# Dirth_Rims_Mend_Orca.net
KiCad netlist of a schematic drawn in EAGLE
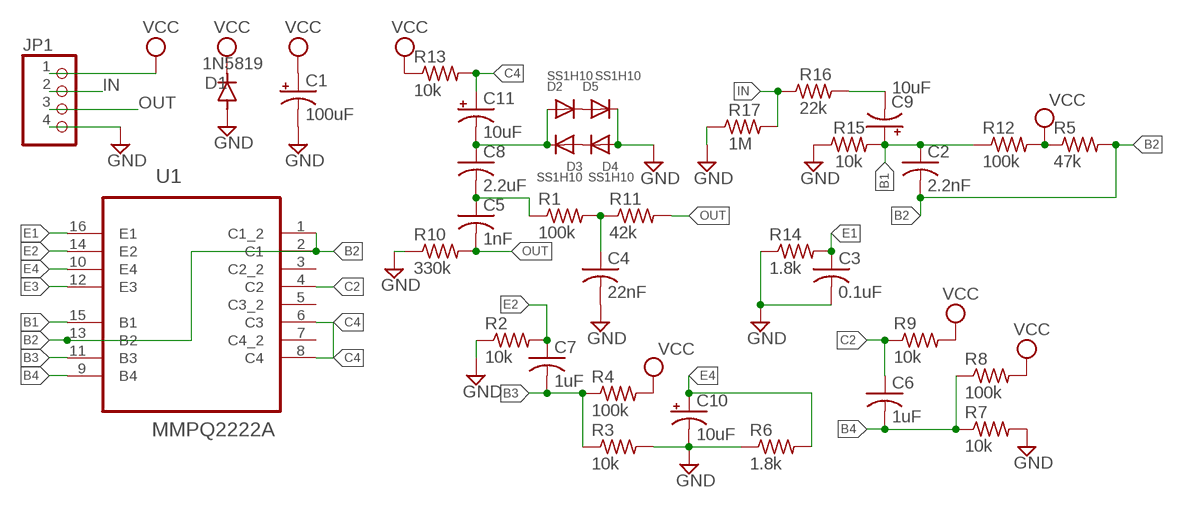
[diagram p0: schematic, sheet 1]

(export (version "E")
  (design (tool "Eeschema 10.0.6"))
  (components
    (comp (ref "C1")
      (value "100uF")
      (footprint "eagle-import:PAN_B_SMD+THRU")
      (libsource (lib "eagle-import") (part "CAP_SMD+THRUPAN_B"))
    )
    (comp (ref "C2")
      (value "2.2nF")
      (footprint "eagle-import:C0603")
      (libsource (lib "eagle-import") (part "C-USC0603"))
    )
    (comp (ref "C3")
      (value "0.1uF")
      (footprint "eagle-import:C0603")
      (libsource (lib "eagle-import") (part "C-USC0603"))
    )
    (comp (ref "C4")
      (value "22nF")
      (footprint "eagle-import:C0603")
      (libsource (lib "eagle-import") (part "C-USC0603"))
    )
    (comp (ref "C5")
      (value "1nF")
      (footprint "eagle-import:C0603")
      (libsource (lib "eagle-import") (part "C-USC0603"))
    )
    (comp (ref "C6")
      (value "1uF")
      (footprint "eagle-import:C0603")
      (libsource (lib "eagle-import") (part "C-USC0603"))
    )
    (comp (ref "C7")
      (value "1uF")
      (footprint "eagle-import:C0603")
      (libsource (lib "eagle-import") (part "C-USC0603"))
    )
    (comp (ref "C8")
      (value "2.2uF")
      (footprint "eagle-import:C0603")
      (libsource (lib "eagle-import") (part "C-USC0603"))
    )
    (comp (ref "C9")
      (value "10uF")
      (footprint "eagle-import:PAN_B_SMD+THRU")
      (libsource (lib "eagle-import") (part "CAP_SMD+THRUPAN_B"))
    )
    (comp (ref "C10")
      (value "10uF")
      (footprint "eagle-import:PAN_B_SMD+THRU")
      (libsource (lib "eagle-import") (part "CAP_SMD+THRUPAN_B"))
    )
    (comp (ref "C11")
      (value "10uF")
      (footprint "eagle-import:PAN_B_SMD+THRU")
      (libsource (lib "eagle-import") (part "CAP_SMD+THRUPAN_B"))
    )
    (comp (ref "D1")
      (value "1N5819")
      (footprint "eagle-import:SOD123")
      (libsource (lib "eagle-import") (part "DIODE-SOD123"))
    )
    (comp (ref "D2")
      (value "SS1H10")
      (footprint "eagle-import:SMADIODE")
      (libsource (lib "eagle-import") (part "DIODESMA"))
    )
    (comp (ref "D3")
      (value "SS1H10")
      (footprint "eagle-import:SMADIODE")
      (libsource (lib "eagle-import") (part "DIODESMA"))
    )
    (comp (ref "D4")
      (value "SS1H10")
      (footprint "eagle-import:SMADIODE")
      (libsource (lib "eagle-import") (part "DIODESMA"))
    )
    (comp (ref "D5")
      (value "SS1H10")
      (footprint "eagle-import:SMADIODE")
      (libsource (lib "eagle-import") (part "DIODESMA"))
    )
    (comp (ref "JP1")
      (value "PINHD-1X4")
      (footprint "eagle-import:1X04")
      (libsource (lib "eagle-import") (part "PINHD-1X4"))
    )
    (comp (ref "R1")
      (value "100k")
      (footprint "eagle-import:R0603")
      (libsource (lib "eagle-import") (part "R-US_R0603"))
    )
    (comp (ref "R2")
      (value "10k")
      (footprint "eagle-import:R0603")
      (libsource (lib "eagle-import") (part "R-US_R0603"))
    )
    (comp (ref "R3")
      (value "10k")
      (footprint "eagle-import:R0603")
      (libsource (lib "eagle-import") (part "R-US_R0603"))
    )
    (comp (ref "R4")
      (value "100k")
      (footprint "eagle-import:R0603")
      (libsource (lib "eagle-import") (part "R-US_R0603"))
    )
    (comp (ref "R5")
      (value "47k")
      (footprint "eagle-import:R0603")
      (libsource (lib "eagle-import") (part "R-US_R0603"))
    )
    (comp (ref "R6")
      (value "1.8k")
      (footprint "eagle-import:R0603")
      (libsource (lib "eagle-import") (part "R-US_R0603"))
    )
    (comp (ref "R7")
      (value "10k")
      (footprint "eagle-import:R0603")
      (libsource (lib "eagle-import") (part "R-US_R0603"))
    )
    (comp (ref "R8")
      (value "100k")
      (footprint "eagle-import:R0603")
      (libsource (lib "eagle-import") (part "R-US_R0603"))
    )
    (comp (ref "R9")
      (value "10k")
      (footprint "eagle-import:R0603")
      (libsource (lib "eagle-import") (part "R-US_R0603"))
    )
    (comp (ref "R10")
      (value "330k")
      (footprint "eagle-import:R0603")
      (libsource (lib "eagle-import") (part "R-US_R0603"))
    )
    (comp (ref "R11")
      (value "42k")
      (footprint "eagle-import:R0603")
      (libsource (lib "eagle-import") (part "R-US_R0603"))
    )
    (comp (ref "R12")
      (value "100k")
      (footprint "eagle-import:R0603")
      (libsource (lib "eagle-import") (part "R-US_R0603"))
    )
    (comp (ref "R13")
      (value "10k")
      (footprint "eagle-import:R0603")
      (libsource (lib "eagle-import") (part "R-US_R0603"))
    )
    (comp (ref "R14")
      (value "1.8k")
      (footprint "eagle-import:R0603")
      (libsource (lib "eagle-import") (part "R-US_R0603"))
    )
    (comp (ref "R15")
      (value "10k")
      (footprint "eagle-import:R0603")
      (libsource (lib "eagle-import") (part "R-US_R0603"))
    )
    (comp (ref "R16")
      (value "22k")
      (footprint "eagle-import:R0603")
      (libsource (lib "eagle-import") (part "R-US_R0603"))
    )
    (comp (ref "R17")
      (value "1M")
      (footprint "eagle-import:R0603")
      (libsource (lib "eagle-import") (part "R-US_R0603"))
    )
    (comp (ref "U1")
      (value "MMPQ2222A")
      (footprint "eagle-import:SOIC127P600X175-16N")
      (fields (field (name "MF") "ON Semiconductor"))
      (libsource (lib "eagle-import") (part "MMPQ2222A"))
    )
  )
  (nets
    (net (code "1") (name "B1") (class "Default")
      (node (ref "C2") (pin "1") (pinfunction "1_1") (pintype "passive"))
      (node (ref "C9") (pin "+") (pinfunction "+_+") (pintype "passive"))
      (node (ref "C9") (pin "++") (pinfunction "+_++") (pintype "passive"))
      (node (ref "R12") (pin "1") (pinfunction "1_1") (pintype "passive"))
      (node (ref "R15") (pin "2") (pinfunction "2_2") (pintype "passive"))
      (node (ref "U1") (pin "15") (pinfunction "B1_15") (pintype "passive"))
    )
    (net (code "2") (name "B2") (class "Default")
      (node (ref "C2") (pin "2") (pinfunction "2_2") (pintype "passive"))
      (node (ref "R5") (pin "2") (pinfunction "2_2") (pintype "passive"))
      (node (ref "U1") (pin "1") (pinfunction "C1_2_1") (pintype "passive"))
      (node (ref "U1") (pin "13") (pinfunction "B2_13") (pintype "passive"))
      (node (ref "U1") (pin "2") (pinfunction "C1_2") (pintype "passive"))
    )
    (net (code "3") (name "B3") (class "Default")
      (node (ref "C7") (pin "2") (pinfunction "2_2") (pintype "passive"))
      (node (ref "R3") (pin "1") (pinfunction "1_1") (pintype "passive"))
      (node (ref "R4") (pin "1") (pinfunction "1_1") (pintype "passive"))
      (node (ref "U1") (pin "11") (pinfunction "B3_11") (pintype "passive"))
    )
    (net (code "4") (name "B4") (class "Default")
      (node (ref "C6") (pin "2") (pinfunction "2_2") (pintype "passive"))
      (node (ref "R7") (pin "1") (pinfunction "1_1") (pintype "passive"))
      (node (ref "R8") (pin "1") (pinfunction "1_1") (pintype "passive"))
      (node (ref "U1") (pin "9") (pinfunction "B4_9") (pintype "passive"))
    )
    (net (code "5") (name "C2") (class "Default")
      (node (ref "C6") (pin "1") (pinfunction "1_1") (pintype "passive"))
      (node (ref "R9") (pin "1") (pinfunction "1_1") (pintype "passive"))
      (node (ref "U1") (pin "4") (pinfunction "C2_4") (pintype "passive"))
    )
    (net (code "6") (name "C4") (class "Default")
      (node (ref "C11") (pin "+") (pinfunction "+_+") (pintype "passive"))
      (node (ref "C11") (pin "++") (pinfunction "+_++") (pintype "passive"))
      (node (ref "R13") (pin "2") (pinfunction "2_2") (pintype "passive"))
      (node (ref "U1") (pin "6") (pinfunction "C3_6") (pintype "passive"))
      (node (ref "U1") (pin "8") (pinfunction "C4_8") (pintype "passive"))
    )
    (net (code "7") (name "E1") (class "Default")
      (node (ref "C3") (pin "1") (pinfunction "1_1") (pintype "passive"))
      (node (ref "R14") (pin "2") (pinfunction "2_2") (pintype "passive"))
      (node (ref "U1") (pin "16") (pinfunction "E1_16") (pintype "passive"))
    )
    (net (code "8") (name "E2") (class "Default")
      (node (ref "C7") (pin "1") (pinfunction "1_1") (pintype "passive"))
      (node (ref "R2") (pin "2") (pinfunction "2_2") (pintype "passive"))
      (node (ref "U1") (pin "14") (pinfunction "E2_14") (pintype "passive"))
    )
    (net (code "9") (name "E3") (class "Default")
      (node (ref "U1") (pin "12") (pinfunction "E3_12") (pintype "passive"))
    )
    (net (code "10") (name "E4") (class "Default")
      (node (ref "C10") (pin "+") (pinfunction "+_+") (pintype "passive"))
      (node (ref "C10") (pin "++") (pinfunction "+_++") (pintype "passive"))
      (node (ref "R6") (pin "2") (pinfunction "2_2") (pintype "passive"))
      (node (ref "U1") (pin "10") (pinfunction "E4_10") (pintype "passive"))
    )
    (net (code "11") (name "GND") (class "Default")
      (node (ref "C1") (pin "-") (pinfunction "-_-") (pintype "passive"))
      (node (ref "C1") (pin "--") (pinfunction "-_--") (pintype "passive"))
      (node (ref "C10") (pin "-") (pinfunction "-_-") (pintype "passive"))
      (node (ref "C10") (pin "--") (pinfunction "-_--") (pintype "passive"))
      (node (ref "C3") (pin "2") (pinfunction "2_2") (pintype "passive"))
      (node (ref "C4") (pin "2") (pinfunction "2_2") (pintype "passive"))
      (node (ref "D1") (pin "A") (pinfunction "A_A") (pintype "passive"))
      (node (ref "D4") (pin "A") (pinfunction "A_A") (pintype "passive"))
      (node (ref "D5") (pin "C") (pinfunction "C_C") (pintype "passive"))
      (node (ref "JP1") (pin "4") (pinfunction "4_4") (pintype "passive"))
      (node (ref "R10") (pin "1") (pinfunction "1_1") (pintype "passive"))
      (node (ref "R14") (pin "1") (pinfunction "1_1") (pintype "passive"))
      (node (ref "R15") (pin "1") (pinfunction "1_1") (pintype "passive"))
      (node (ref "R17") (pin "1") (pinfunction "1_1") (pintype "passive"))
      (node (ref "R2") (pin "1") (pinfunction "1_1") (pintype "passive"))
      (node (ref "R3") (pin "2") (pinfunction "2_2") (pintype "passive"))
      (node (ref "R6") (pin "1") (pinfunction "1_1") (pintype "passive"))
      (node (ref "R7") (pin "2") (pinfunction "2_2") (pintype "passive"))
    )
    (net (code "12") (name "IN") (class "Default")
      (node (ref "JP1") (pin "2") (pinfunction "2_2") (pintype "passive"))
      (node (ref "R16") (pin "1") (pinfunction "1_1") (pintype "passive"))
      (node (ref "R17") (pin "2") (pinfunction "2_2") (pintype "passive"))
    )
    (net (code "13") (name "Net-(C4-Pad1)") (class "Default")
      (node (ref "C4") (pin "1") (pinfunction "1_1") (pintype "passive"))
      (node (ref "R1") (pin "2") (pinfunction "2_2") (pintype "passive"))
      (node (ref "R11") (pin "1") (pinfunction "1_1") (pintype "passive"))
    )
    (net (code "14") (name "Net-(C5-Pad1)") (class "Default")
      (node (ref "C5") (pin "1") (pinfunction "1_1") (pintype "passive"))
      (node (ref "C8") (pin "2") (pinfunction "2_2") (pintype "passive"))
      (node (ref "R1") (pin "1") (pinfunction "1_1") (pintype "passive"))
    )
    (net (code "15") (name "Net-(C9---Pad--)") (class "Default")
      (node (ref "C9") (pin "-") (pinfunction "-_-") (pintype "passive"))
      (node (ref "C9") (pin "--") (pinfunction "-_--") (pintype "passive"))
      (node (ref "R16") (pin "2") (pinfunction "2_2") (pintype "passive"))
    )
    (net (code "16") (name "Net-(C11---Pad--)") (class "Default")
      (node (ref "C11") (pin "-") (pinfunction "-_-") (pintype "passive"))
      (node (ref "C11") (pin "--") (pinfunction "-_--") (pintype "passive"))
      (node (ref "C8") (pin "1") (pinfunction "1_1") (pintype "passive"))
      (node (ref "D2") (pin "A") (pinfunction "A_A") (pintype "passive"))
      (node (ref "D3") (pin "C") (pinfunction "C_C") (pintype "passive"))
    )
    (net (code "17") (name "Net-(D2-PadC)") (class "Default")
      (node (ref "D2") (pin "C") (pinfunction "C_C") (pintype "passive"))
      (node (ref "D5") (pin "A") (pinfunction "A_A") (pintype "passive"))
    )
    (net (code "18") (name "Net-(D3-PadA)") (class "Default")
      (node (ref "D3") (pin "A") (pinfunction "A_A") (pintype "passive"))
      (node (ref "D4") (pin "C") (pinfunction "C_C") (pintype "passive"))
    )
    (net (code "19") (name "OUT") (class "Default")
      (node (ref "C5") (pin "2") (pinfunction "2_2") (pintype "passive"))
      (node (ref "JP1") (pin "3") (pinfunction "3_3") (pintype "passive"))
      (node (ref "R10") (pin "2") (pinfunction "2_2") (pintype "passive"))
      (node (ref "R11") (pin "2") (pinfunction "2_2") (pintype "passive"))
    )
    (net (code "20") (name "VCC") (class "Default")
      (node (ref "C1") (pin "+") (pinfunction "+_+") (pintype "passive"))
      (node (ref "C1") (pin "++") (pinfunction "+_++") (pintype "passive"))
      (node (ref "D1") (pin "C") (pinfunction "C_C") (pintype "passive"))
      (node (ref "JP1") (pin "1") (pinfunction "1_1") (pintype "passive"))
      (node (ref "R12") (pin "2") (pinfunction "2_2") (pintype "passive"))
      (node (ref "R13") (pin "1") (pinfunction "1_1") (pintype "passive"))
      (node (ref "R4") (pin "2") (pinfunction "2_2") (pintype "passive"))
      (node (ref "R5") (pin "1") (pinfunction "1_1") (pintype "passive"))
      (node (ref "R8") (pin "2") (pinfunction "2_2") (pintype "passive"))
      (node (ref "R9") (pin "2") (pinfunction "2_2") (pintype "passive"))
    )
    (net (code "21") (name "unconnected-(U1-C2_2-Pad3)") (class "Default")
      (node (ref "U1") (pin "3") (pinfunction "C2_2_3") (pintype "passive"))
    )
    (net (code "22") (name "unconnected-(U1-C3_2-Pad5)") (class "Default")
      (node (ref "U1") (pin "5") (pinfunction "C3_2_5") (pintype "passive"))
    )
    (net (code "23") (name "unconnected-(U1-C4_2-Pad7)") (class "Default")
      (node (ref "U1") (pin "7") (pinfunction "C4_2_7") (pintype "passive"))
    )
  )
)
